# Real_Time_Clock.net
KiCad netlist of a schematic drawn in Altium Designer
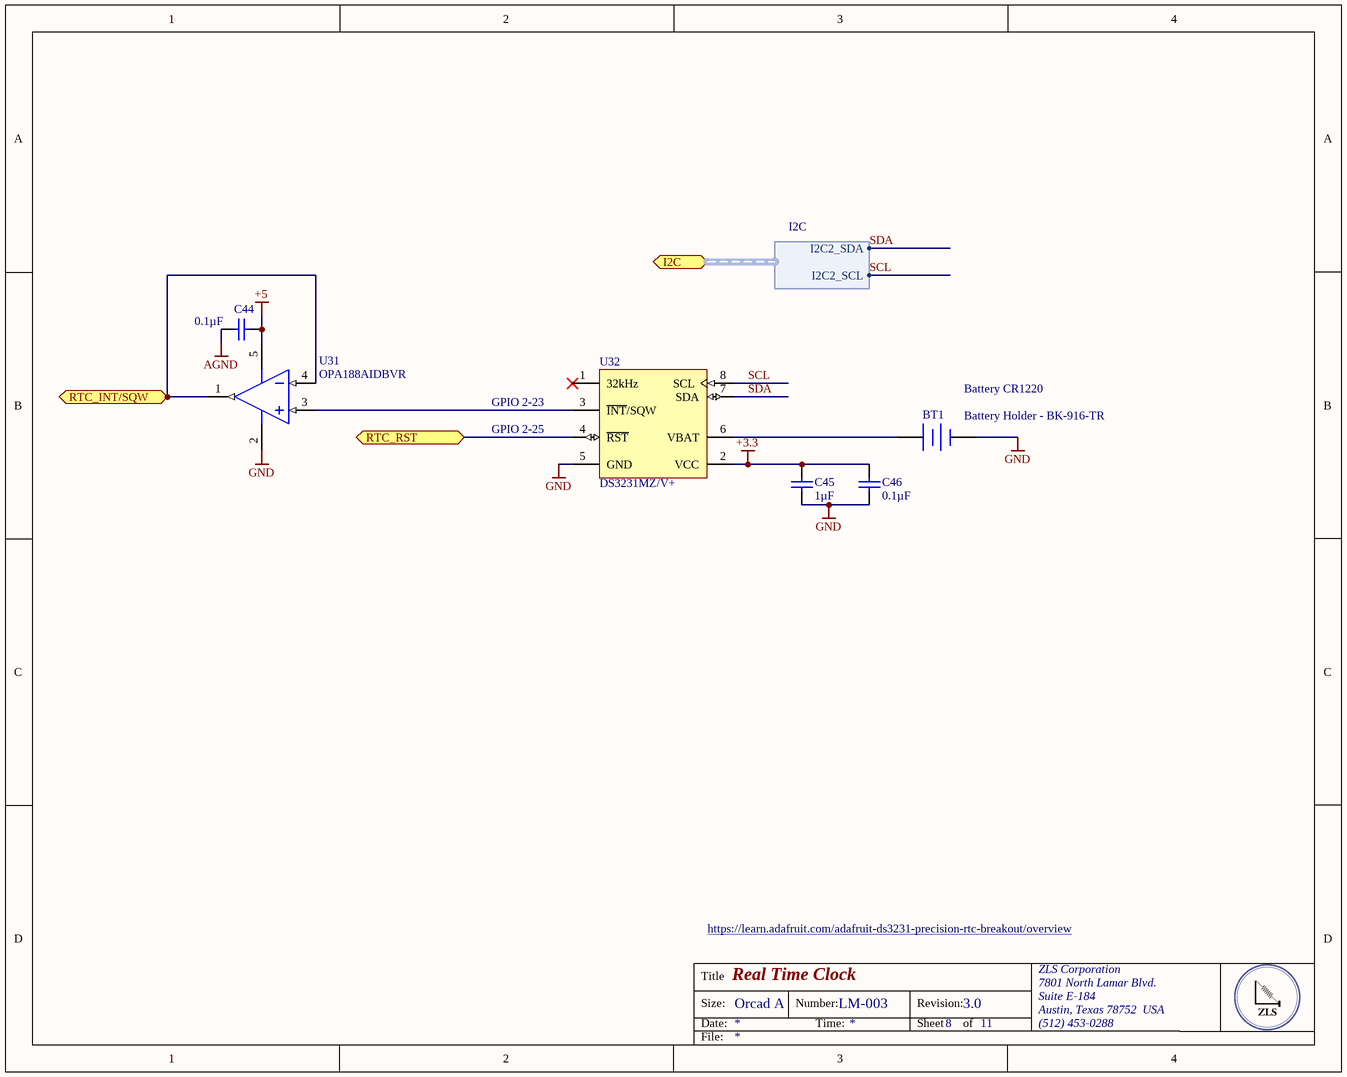
[diagram p0: Real Time Clock.SchDoc]

(export (version "E")
  (design (tool "Eeschema 10.0.6"))
  (components
    (comp (ref "BT1")
      (value "Battery Holder - BK-916-TR")
      (footprint "BK-916-TR")
      (description "CR1220, 1225 BATTERY RETAINER W/")
      (libsource (lib "Miscellaneous Devices") (part "Battery"))
    )
    (comp (ref "C44")
      (value "CAP CER 0.1UF 16V X7R 0805")
      (footprint "CAPC0805(2012)145_N")
      (fields
        (field (name "TOLERANCE") "±10%")
        (field (name "MANUFACTURER") "Murata Electronics North America")
        (field (name "MANUFACTURER PART NUMBER") "GRM219R71C104KA01D")
        (field (name "CAPACITANCE") "0.1µF")
      )
      (libsource (lib "Altium Content Vault") (part "CMP-1036-04795-1"))
    )
    (comp (ref "C45")
      (value "CAP 1uF 25V 0805(2012)")
      (footprint "CAPC0805(2012)100_M")
      (description "CAP 1uF 25V ±10% 0805 (2012 Metric) Thickness 1mm SMD")
      (fields
        (field (name "MANUFACTURER") "Murata Electronics North America")
        (field (name "MANUFACTURER PART NUMBER") "GRM21BR71E105KA99L")
        (field (name "CAPACITANCE") "1µF")
      )
      (libsource (lib "Altium Content Vault") (part "CMP-1036-04754-1"))
    )
    (comp (ref "C46")
      (value "CAP 100nF 25V 0805(2012)")
      (footprint "CAPC0805(2012)100_N")
      (description "CAP 100nF 25V -20% to +80% 0805 (2012 Metric) Thickness 1mm SMD")
      (fields
        (field (name "MANUFACTURER") "Murata Electronics North America")
        (field (name "MANUFACTURER PART NUMBER") "GRM21BR71E104KA01L")
        (field (name "CAPACITANCE") "0.1µF")
      )
      (libsource (lib "Altium Content Vault") (part "CMP-1036-04416-1"))
    )
    (comp (ref "U31")
      (value "OPA188AIDBVR")
      (footprint "DBV0005A_M")
      (fields (field (name "MANUFACTURER") "Texas Instruments"))
      (libsource (lib "Altium Content Vault") (part "CMP-0809-00005-2"))
    )
    (comp (ref "U32")
      (value "DS3231MZ/V+")
      (footprint "S8MK+1_N")
      (libsource (lib "Altium Content Vault") (part "CMP-0254-00374-1"))
    )
  )
  (nets
    (net (code "2") (name "+3.3") (class "Default")
      (node (ref "C45") (pin "1") (pinfunction "1_1") (pintype "passive"))
      (node (ref "C46") (pin "1") (pinfunction "1_1") (pintype "passive"))
      (node (ref "U32") (pin "2") (pinfunction "VCC_2") (pintype "power_in"))
    )
    (net (code "3") (name "+5") (class "Default")
      (node (ref "C44") (pin "2") (pinfunction "2_2") (pintype "passive"))
      (node (ref "U31") (pin "5") (pinfunction "V+_5") (pintype "power_in"))
    )
    (net (code "4") (name "/RTC_INT{slash}SQW") (class "Default")
      (node (ref "U31") (pin "1") (pinfunction "OUT_1") (pintype "output"))
      (node (ref "U31") (pin "4") (pinfunction "IN-_4") (pintype "input"))
    )
    (net (code "5") (name "/RTC_RST") (class "Default")
      (node (ref "U32") (pin "4") (pinfunction "~{RST}_4") (pintype "bidirectional"))
    )
    (net (code "6") (name "/SCL") (class "Default")
      (node (ref "U32") (pin "8") (pinfunction "SCL_8") (pintype "input"))
    )
    (net (code "7") (name "/SDA") (class "Default")
      (node (ref "U32") (pin "7") (pinfunction "SDA_7") (pintype "bidirectional"))
    )
    (net (code "9") (name "AGND") (class "Default")
      (node (ref "C44") (pin "1") (pinfunction "1_1") (pintype "passive"))
    )
    (net (code "10") (name "GND") (class "Default")
      (node (ref "BT1") (pin "2") (pinfunction "-_2") (pintype "passive"))
      (node (ref "C45") (pin "2") (pinfunction "2_2") (pintype "passive"))
      (node (ref "C46") (pin "2") (pinfunction "2_2") (pintype "passive"))
      (node (ref "U31") (pin "2") (pinfunction "V-_2") (pintype "power_in"))
      (node (ref "U32") (pin "5") (pinfunction "GND_5") (pintype "power_in"))
    )
    (net (code "11") (name "Net-(BT1-+)") (class "Default")
      (node (ref "BT1") (pin "1") (pinfunction "+_1") (pintype "passive"))
      (node (ref "U32") (pin "6") (pinfunction "VBAT_6") (pintype "power_in"))
    )
    (net (code "12") (name "Net-(U31-IN+)") (class "Default")
      (node (ref "U31") (pin "3") (pinfunction "IN+_3") (pintype "input"))
      (node (ref "U32") (pin "3") (pinfunction "~{INT}/SQW_3") (pintype "open_collector"))
    )
    (net (code "13") (name "unconnected-(U32-32kHz-Pad1)") (class "Default")
      (node (ref "U32") (pin "1") (pinfunction "32kHz_1") (pintype "open_collector+no_connect"))
    )
  )
)
